# SCH_Battery_level_indicator_2025-08-23.net
KiCad netlist of a schematic drawn in EasyEDA
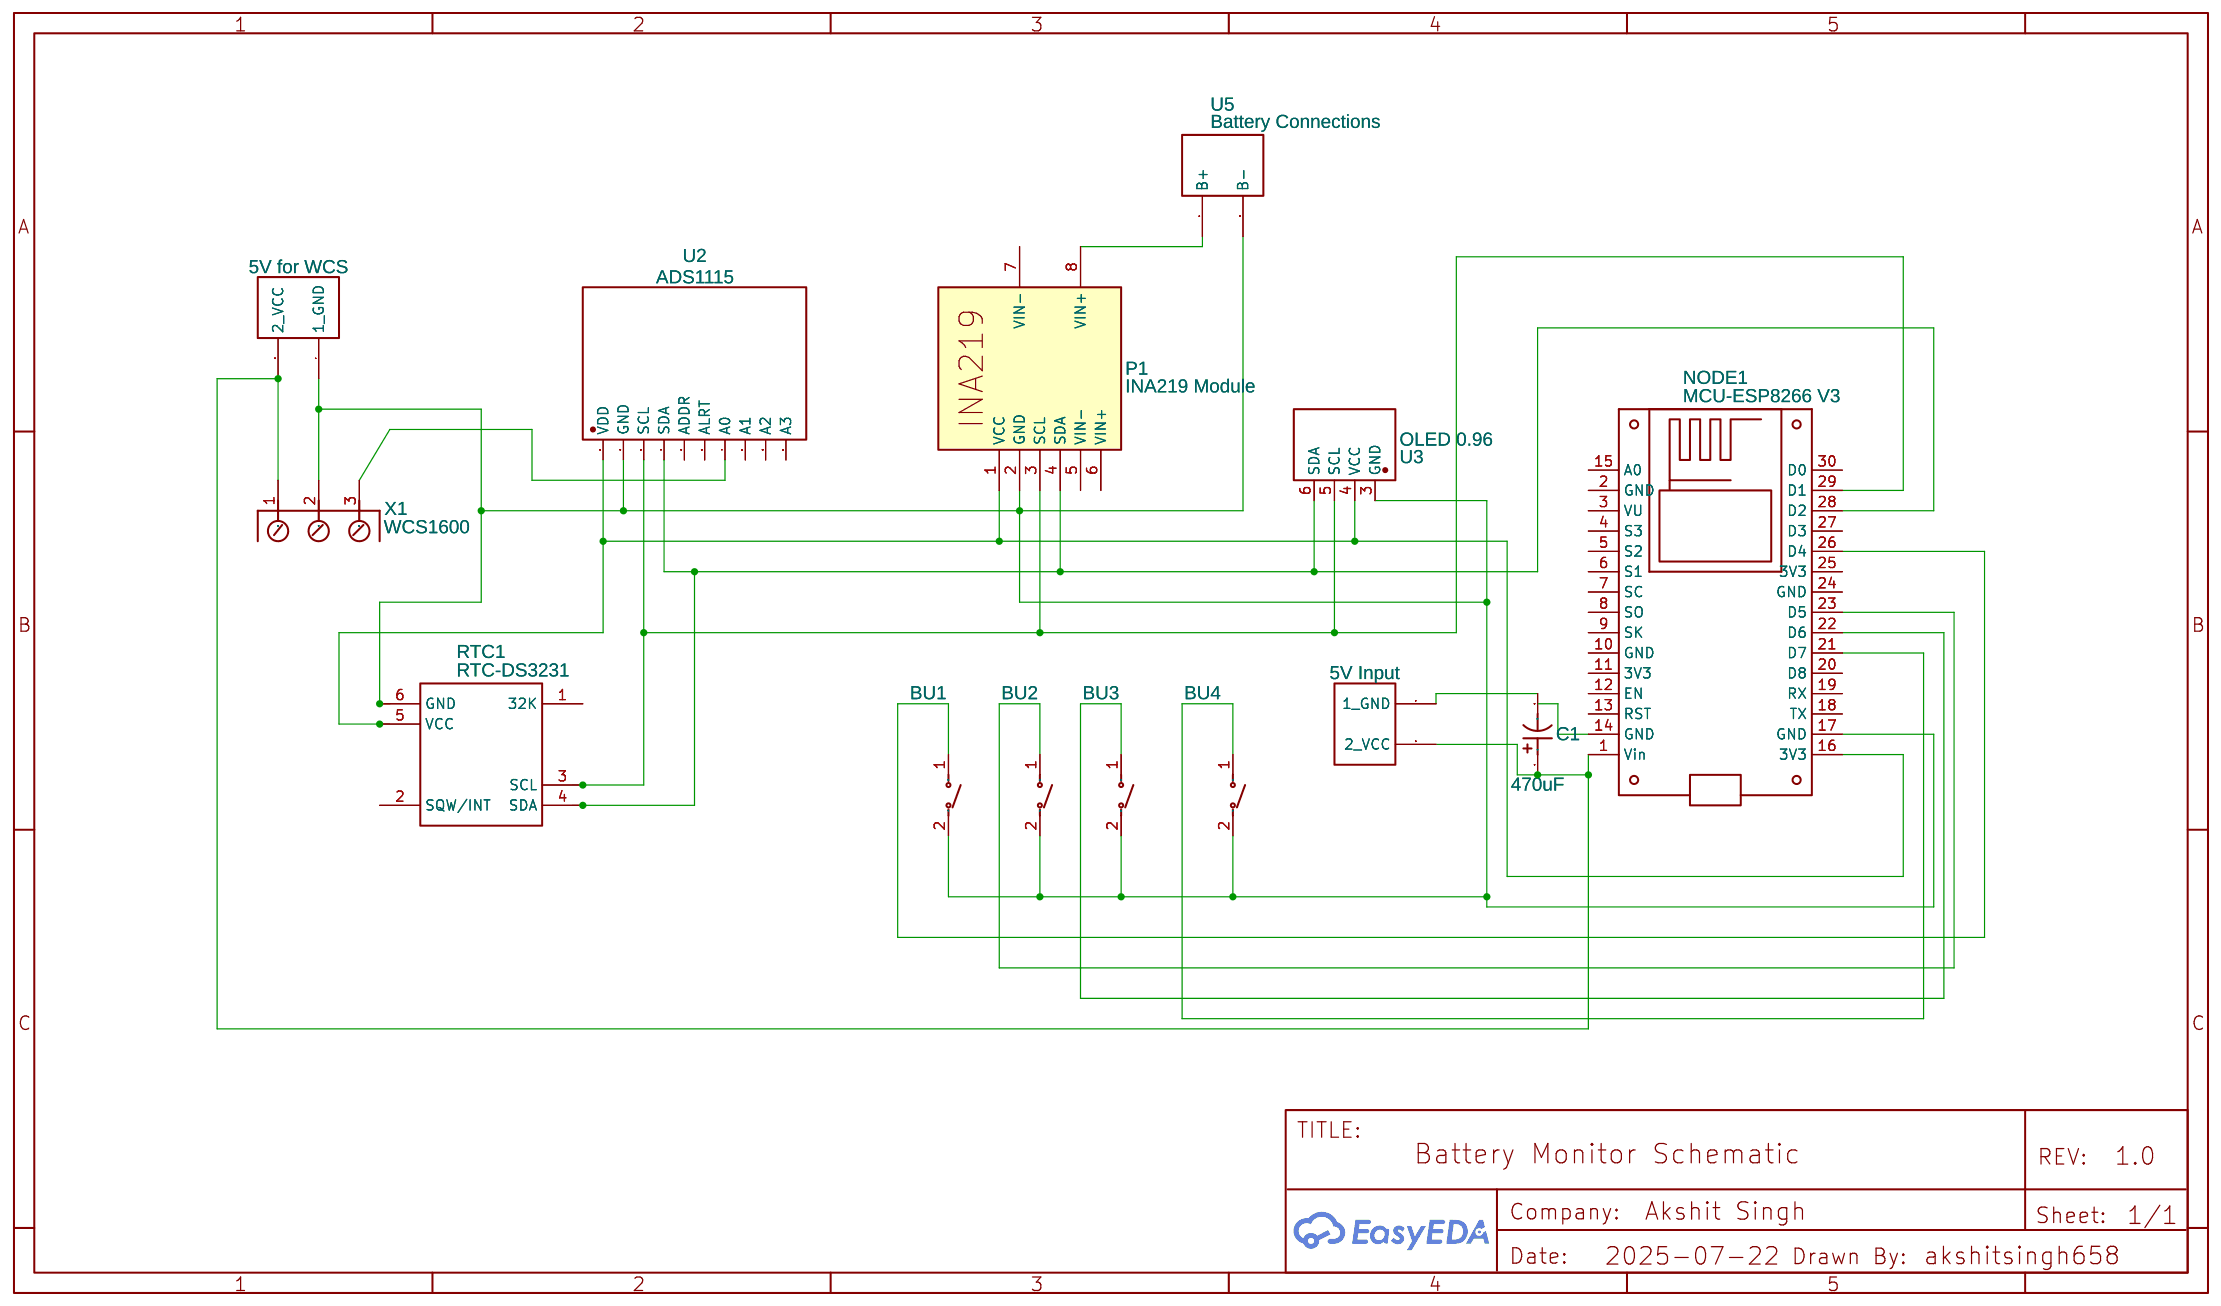
[diagram p0: schematic sheet]

(export (version "E")
  (design (tool "Eeschema 10.0.6"))
  (components
    (comp (ref "BU1")
      (value "Right Reverse")
      (fields (field (name "Manufacturer Part") "BUTTON2-3*6*2.5"))
      (libsource (lib "") (part "Pushbutton"))
    )
    (comp (ref "BU2")
      (value "Right Reverse")
      (fields (field (name "Manufacturer Part") "BUTTON2-3*6*2.5"))
      (libsource (lib "") (part "Pushbutton"))
    )
    (comp (ref "BU3")
      (value "Right Reverse")
      (fields (field (name "Manufacturer Part") "BUTTON2-3*6*2.5"))
      (libsource (lib "") (part "Pushbutton"))
    )
    (comp (ref "BU4")
      (value "Right Reverse")
      (fields (field (name "Manufacturer Part") "BUTTON2-3*6*2.5"))
      (libsource (lib "") (part "Pushbutton"))
    )
    (comp (ref "C1")
      (value "470uF")
      (fields (field (name "Manufacturer Part") "16V470uF CD110") (field (name "Manufacturer") "HRK(鸿瑞凯电子)"))
      (libsource (lib "") (part "16V470UF CD110"))
    )
    (comp (ref "NODE1") (value "MCU-ESP8266 V3") (libsource (lib "") (part "MCU-ESP8266 V3")))
    (comp (ref "P1") (value "INA219 Module") (libsource (lib "") (part "INA219 Module")))
    (comp (ref "RTC1") (value "RTC-DS3231") (libsource (lib "") (part "RTC-DS3231")))
    (comp (ref "U1") (value "5V Input") (libsource (lib "") (part "Screw terminal block (2)")))
    (comp (ref "U2") (value "ADS1115") (libsource (lib "") (part "ADS1115")))
    (comp (ref "U3")
      (value "OLED 0.96")
      (fields
        (field (name "Manufacturer Part") "ZJY096S0700BG01蓝色")
        (field (name "Manufacturer") "AZDelivery")
      )
      (libsource (lib "") (part "OLED 0.96 COPY"))
    )
    (comp (ref "U4") (value "5V for WCS") (libsource (lib "") (part "Screw terminal block (2)_2")))
    (comp (ref "U5") (value "Battery Connections") (libsource (lib "") (part "Screw terminal block (2)_1")))
    (comp (ref "X1") (value "WCS1600") (libsource (lib "") (part "AKL701_3_15")))
  )
  (nets
    (net (code "1") (name "Net-(NODE1-D1)") (class "Default")
      (node (ref "NODE1") (pin "29") (pinfunction "D1_29") (pintype "unspecified"))
      (node (ref "P1") (pin "3") (pinfunction "SCL_3") (pintype "unspecified"))
      (node (ref "RTC1") (pin "3") (pinfunction "SCL_3") (pintype "unspecified"))
      (node (ref "U2") (pin "3") (pinfunction "SCL_3") (pintype "unspecified"))
      (node (ref "U3") (pin "5") (pinfunction "SCL_5") (pintype "unspecified"))
    )
    (net (code "2") (name "Net-(NODE1-D2)") (class "Default")
      (node (ref "NODE1") (pin "28") (pinfunction "D2_28") (pintype "unspecified"))
      (node (ref "P1") (pin "4") (pinfunction "SDA_4") (pintype "unspecified"))
      (node (ref "RTC1") (pin "4") (pinfunction "SDA_4") (pintype "unspecified"))
      (node (ref "U2") (pin "4") (pinfunction "SDA_4") (pintype "unspecified"))
      (node (ref "U3") (pin "6") (pinfunction "SDA_6") (pintype "unspecified"))
    )
    (net (code "3") (name "Net-(NODE1-D4)") (class "Default")
      (node (ref "BU1") (pin "1") (pinfunction "1_1") (pintype "unspecified"))
      (node (ref "NODE1") (pin "26") (pinfunction "D4_26") (pintype "unspecified"))
    )
    (net (code "4") (name "Net-(NODE1-D5)") (class "Default")
      (node (ref "BU2") (pin "1") (pinfunction "1_1") (pintype "unspecified"))
      (node (ref "NODE1") (pin "23") (pinfunction "D5_23") (pintype "unspecified"))
    )
    (net (code "5") (name "Net-(NODE1-D6)") (class "Default")
      (node (ref "BU3") (pin "1") (pinfunction "1_1") (pintype "unspecified"))
      (node (ref "NODE1") (pin "22") (pinfunction "D6_22") (pintype "unspecified"))
    )
    (net (code "6") (name "Net-(NODE1-D7)") (class "Default")
      (node (ref "BU4") (pin "1") (pinfunction "1_1") (pintype "unspecified"))
      (node (ref "NODE1") (pin "21") (pinfunction "D7_21") (pintype "unspecified"))
    )
    (net (code "7") (name "Net-(NODE1-Vin)") (class "Default")
      (node (ref "C1") (pin "1") (pinfunction "1_1") (pintype "input"))
      (node (ref "NODE1") (pin "1") (pinfunction "Vin_1") (pintype "unspecified"))
      (node (ref "U1") (pin "2") (pinfunction "2_VCC_2") (pintype "unspecified"))
      (node (ref "U4") (pin "2") (pinfunction "2_VCC_2") (pintype "unspecified"))
      (node (ref "X1") (pin "1") (pinfunction "1_1") (pintype "unspecified"))
    )
    (net (code "8") (name "Net-(P1-GND)") (class "Default")
      (node (ref "BU1") (pin "2") (pinfunction "2_2") (pintype "unspecified"))
      (node (ref "BU2") (pin "2") (pinfunction "2_2") (pintype "unspecified"))
      (node (ref "BU3") (pin "2") (pinfunction "2_2") (pintype "unspecified"))
      (node (ref "BU4") (pin "2") (pinfunction "2_2") (pintype "unspecified"))
      (node (ref "NODE1") (pin "17") (pinfunction "GND_17") (pintype "unspecified"))
      (node (ref "P1") (pin "2") (pinfunction "GND_2") (pintype "unspecified"))
      (node (ref "RTC1") (pin "6") (pinfunction "GND_6") (pintype "unspecified"))
      (node (ref "U2") (pin "2") (pinfunction "GND_2") (pintype "unspecified"))
      (node (ref "U3") (pin "3") (pinfunction "GND_3") (pintype "unspecified"))
      (node (ref "U4") (pin "1") (pinfunction "1_GND_1") (pintype "unspecified"))
      (node (ref "U5") (pin "2") (pinfunction "B-_2") (pintype "unspecified"))
      (node (ref "X1") (pin "2") (pinfunction "2_2") (pintype "unspecified"))
    )
    (net (code "9") (name "Net-(P1-VCC)") (class "Default")
      (node (ref "NODE1") (pin "16") (pinfunction "3V3_16") (pintype "unspecified"))
      (node (ref "P1") (pin "1") (pinfunction "VCC_1") (pintype "unspecified"))
      (node (ref "RTC1") (pin "5") (pinfunction "VCC_5") (pintype "unspecified"))
      (node (ref "U2") (pin "1") (pinfunction "VDD_1") (pintype "unspecified"))
      (node (ref "U3") (pin "4") (pinfunction "VCC_4") (pintype "unspecified"))
    )
    (net (code "10") (name "Net-(U1-1_GND)") (class "Default")
      (node (ref "C1") (pin "2") (pinfunction "2_2") (pintype "input"))
      (node (ref "U1") (pin "1") (pinfunction "1_GND_1") (pintype "unspecified"))
    )
    (net (code "11") (name "Net-(U2-A0)") (class "Default")
      (node (ref "U2") (pin "7") (pinfunction "A0_7") (pintype "unspecified"))
      (node (ref "X1") (pin "3") (pinfunction "3_3") (pintype "unspecified"))
    )
    (net (code "12") (name "Net-(U5-B+)") (class "Default")
      (node (ref "P1") (pin "8") (pinfunction "VIN+_8") (pintype "unspecified"))
      (node (ref "U5") (pin "1") (pinfunction "B+_1") (pintype "unspecified"))
    )
    (net (code "13") (name "unconnected-(NODE1-3V3-Pad11)") (class "Default")
      (node (ref "NODE1") (pin "11") (pinfunction "3V3_11") (pintype "unspecified"))
    )
    (net (code "14") (name "unconnected-(NODE1-3V3-Pad25)") (class "Default")
      (node (ref "NODE1") (pin "25") (pinfunction "3V3_25") (pintype "unspecified"))
    )
    (net (code "15") (name "unconnected-(NODE1-A0-Pad15)") (class "Default")
      (node (ref "NODE1") (pin "15") (pinfunction "A0_15") (pintype "unspecified"))
    )
    (net (code "16") (name "unconnected-(NODE1-D0-Pad30)") (class "Default")
      (node (ref "NODE1") (pin "30") (pinfunction "D0_30") (pintype "unspecified"))
    )
    (net (code "17") (name "unconnected-(NODE1-D3-Pad27)") (class "Default")
      (node (ref "NODE1") (pin "27") (pinfunction "D3_27") (pintype "unspecified"))
    )
    (net (code "18") (name "unconnected-(NODE1-D8-Pad20)") (class "Default")
      (node (ref "NODE1") (pin "20") (pinfunction "D8_20") (pintype "unspecified"))
    )
    (net (code "19") (name "unconnected-(NODE1-EN-Pad12)") (class "Default")
      (node (ref "NODE1") (pin "12") (pinfunction "EN_12") (pintype "unspecified"))
    )
    (net (code "20") (name "unconnected-(NODE1-GND-Pad2)") (class "Default")
      (node (ref "NODE1") (pin "2") (pinfunction "GND_2") (pintype "unspecified"))
    )
    (net (code "21") (name "unconnected-(NODE1-GND-Pad10)") (class "Default")
      (node (ref "NODE1") (pin "10") (pinfunction "GND_10") (pintype "unspecified"))
    )
    (net (code "22") (name "unconnected-(NODE1-GND-Pad14)") (class "Default")
      (node (ref "NODE1") (pin "14") (pinfunction "GND_14") (pintype "unspecified"))
    )
    (net (code "23") (name "unconnected-(NODE1-GND-Pad24)") (class "Default")
      (node (ref "NODE1") (pin "24") (pinfunction "GND_24") (pintype "unspecified"))
    )
    (net (code "24") (name "unconnected-(NODE1-RST-Pad13)") (class "Default")
      (node (ref "NODE1") (pin "13") (pinfunction "RST_13") (pintype "unspecified"))
    )
    (net (code "25") (name "unconnected-(NODE1-RX-Pad19)") (class "Default")
      (node (ref "NODE1") (pin "19") (pinfunction "RX_19") (pintype "unspecified"))
    )
    (net (code "26") (name "unconnected-(NODE1-S1-Pad6)") (class "Default")
      (node (ref "NODE1") (pin "6") (pinfunction "S1_6") (pintype "unspecified"))
    )
    (net (code "27") (name "unconnected-(NODE1-S2-Pad5)") (class "Default")
      (node (ref "NODE1") (pin "5") (pinfunction "S2_5") (pintype "unspecified"))
    )
    (net (code "28") (name "unconnected-(NODE1-S3-Pad4)") (class "Default")
      (node (ref "NODE1") (pin "4") (pinfunction "S3_4") (pintype "unspecified"))
    )
    (net (code "29") (name "unconnected-(NODE1-SC-Pad7)") (class "Default")
      (node (ref "NODE1") (pin "7") (pinfunction "SC_7") (pintype "unspecified"))
    )
    (net (code "30") (name "unconnected-(NODE1-SK-Pad9)") (class "Default")
      (node (ref "NODE1") (pin "9") (pinfunction "SK_9") (pintype "unspecified"))
    )
    (net (code "31") (name "unconnected-(NODE1-SO-Pad8)") (class "Default")
      (node (ref "NODE1") (pin "8") (pinfunction "SO_8") (pintype "unspecified"))
    )
    (net (code "32") (name "unconnected-(NODE1-TX-Pad18)") (class "Default")
      (node (ref "NODE1") (pin "18") (pinfunction "TX_18") (pintype "unspecified"))
    )
    (net (code "33") (name "unconnected-(NODE1-VU-Pad3)") (class "Default")
      (node (ref "NODE1") (pin "3") (pinfunction "VU_3") (pintype "unspecified"))
    )
    (net (code "34") (name "unconnected-(P1-VIN+-Pad6)") (class "Default")
      (node (ref "P1") (pin "6") (pinfunction "VIN+_6") (pintype "unspecified"))
    )
    (net (code "35") (name "unconnected-(P1-VIN--Pad5)") (class "Default")
      (node (ref "P1") (pin "5") (pinfunction "VIN-_5") (pintype "unspecified"))
    )
    (net (code "36") (name "unconnected-(P1-VIN--Pad7)") (class "Default")
      (node (ref "P1") (pin "7") (pinfunction "VIN-_7") (pintype "unspecified"))
    )
    (net (code "37") (name "unconnected-(RTC1-32K-Pad1)") (class "Default")
      (node (ref "RTC1") (pin "1") (pinfunction "32K_1") (pintype "unspecified"))
    )
    (net (code "38") (name "unconnected-(RTC1-SQW{slash}INT-Pad2)") (class "Default")
      (node (ref "RTC1") (pin "2") (pinfunction "SQW/INT_2") (pintype "unspecified"))
    )
    (net (code "39") (name "unconnected-(U2-A1-Pad8)") (class "Default")
      (node (ref "U2") (pin "8") (pinfunction "A1_8") (pintype "unspecified"))
    )
    (net (code "40") (name "unconnected-(U2-A2-Pad9)") (class "Default")
      (node (ref "U2") (pin "9") (pinfunction "A2_9") (pintype "unspecified"))
    )
    (net (code "41") (name "unconnected-(U2-A3-Pad10)") (class "Default")
      (node (ref "U2") (pin "10") (pinfunction "A3_10") (pintype "unspecified"))
    )
    (net (code "42") (name "unconnected-(U2-ADDR-Pad5)") (class "Default")
      (node (ref "U2") (pin "5") (pinfunction "ADDR_5") (pintype "unspecified"))
    )
    (net (code "43") (name "unconnected-(U2-ALRT-Pad6)") (class "Default")
      (node (ref "U2") (pin "6") (pinfunction "ALRT_6") (pintype "unspecified"))
    )
  )
)
